# BATTERY_BOARD.net
KiCad netlist of a schematic drawn in Altium Designer
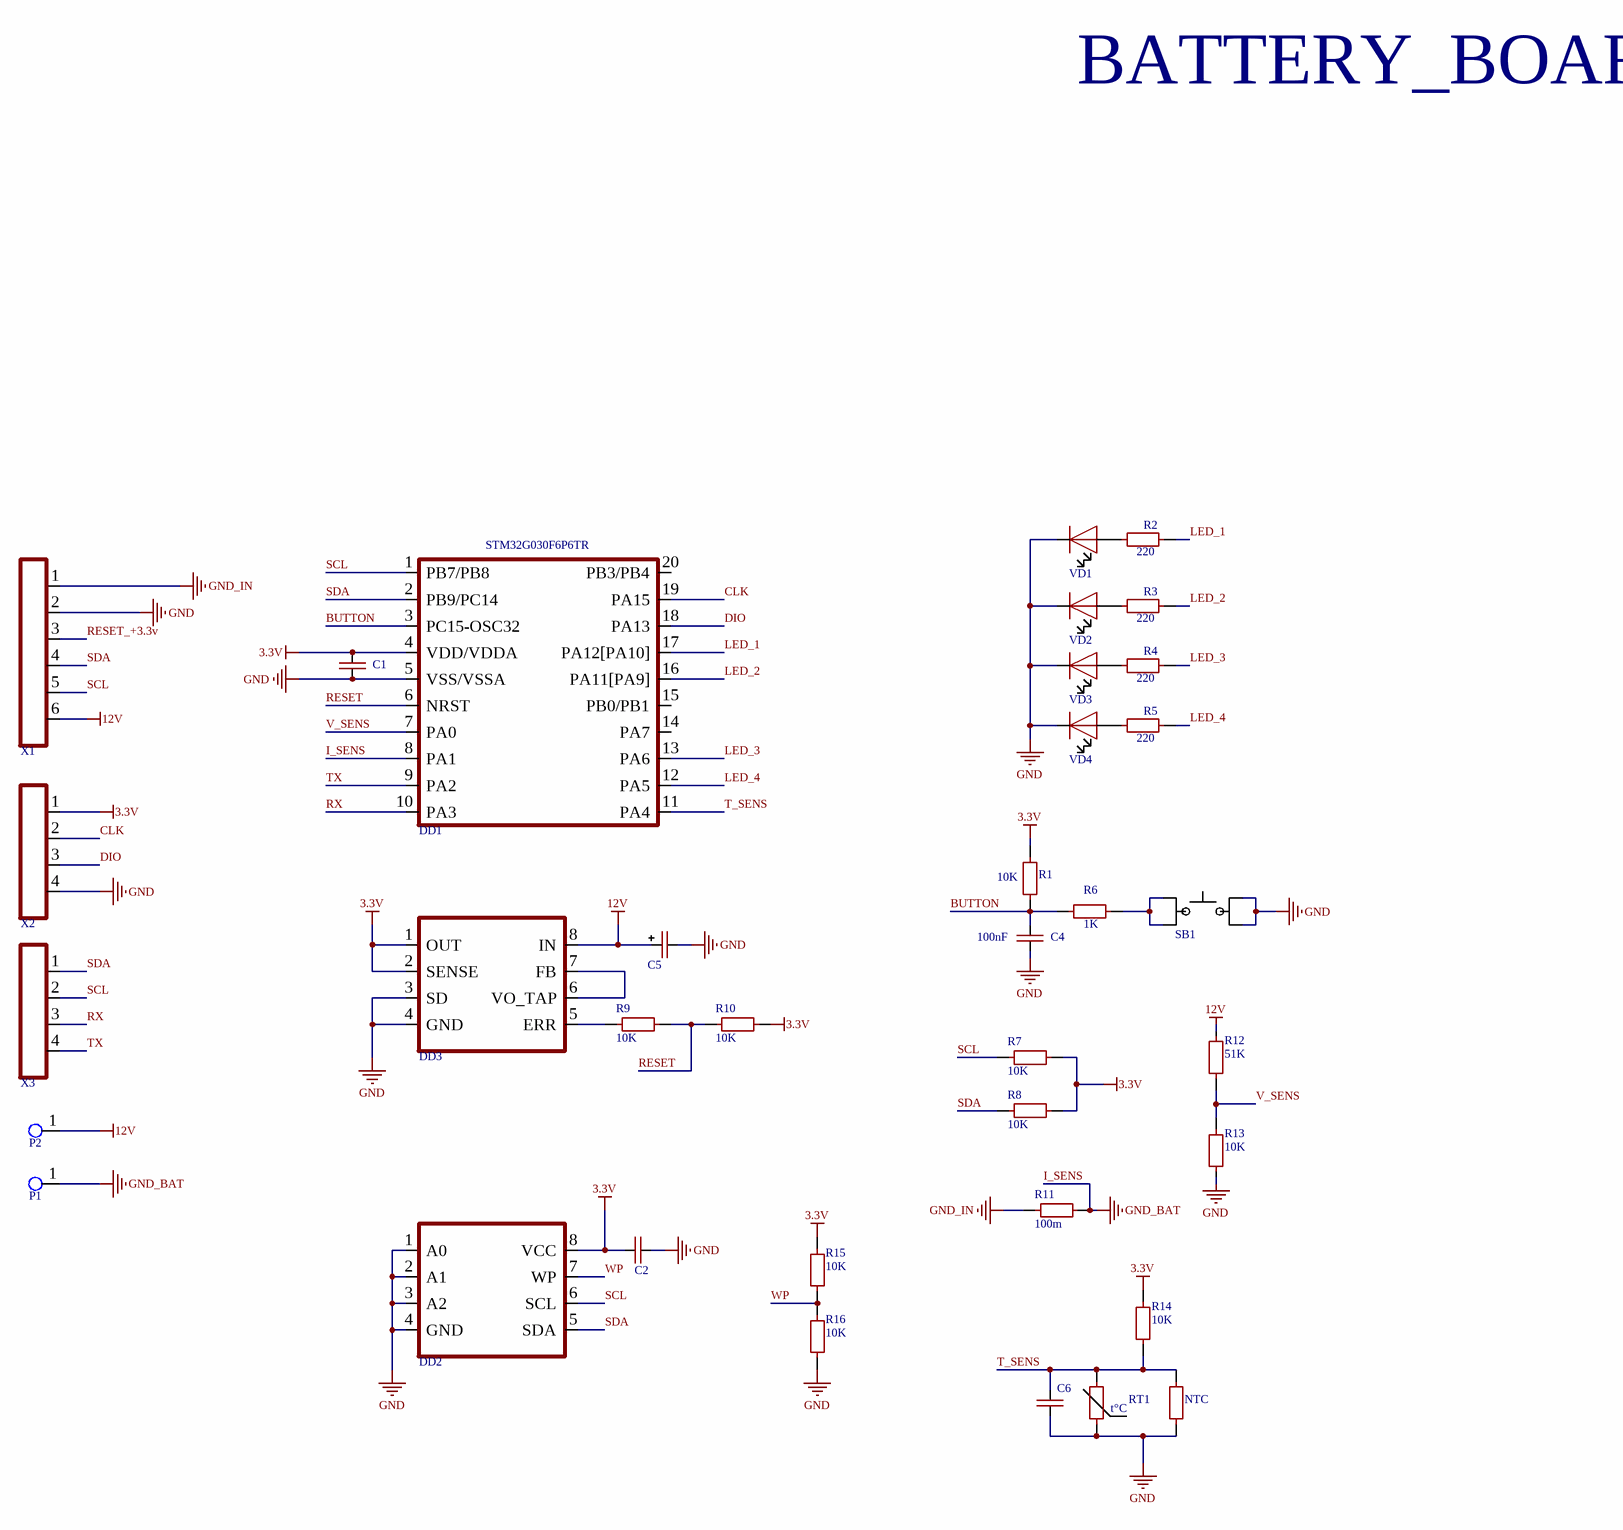
[diagram p0: BATTERY_BOARD.SchDoc]

(export (version "E")
  (design (tool "Eeschema 10.0.6"))
  (components
    (comp (ref "C1")
      (value "CAP-NON-POLAR")
      (footprint "CAP-0603")
      (libsource (lib "PASSIVE_COMPONENTS") (part "CAP-NON-POLAR"))
    )
    (comp (ref "C2")
      (value "CAP-NON-POLAR")
      (footprint "CAP-0603")
      (libsource (lib "PASSIVE_COMPONENTS") (part "CAP-NON-POLAR"))
    )
    (comp (ref "C4")
      (value "100nF")
      (footprint "CAP-0603")
      (libsource (lib "PASSIVE_COMPONENTS") (part "CAP-NON-POLAR"))
    )
    (comp (ref "C5")
      (value "CAP-POLAR")
      (footprint "CAP-TAN-C")
      (libsource (lib "PASSIVE_COMPONENTS") (part "CAP-POLAR"))
    )
    (comp (ref "C6")
      (value "CAP-NON-POLAR")
      (footprint "CAP-0805")
      (libsource (lib "PASSIVE_COMPONENTS") (part "CAP-NON-POLAR"))
    )
    (comp (ref "DD1")
      (value "STM32G030F6P6TR")
      (footprint "TSSOP-20")
      (libsource (lib "STM32G030F6P6TR") (part "STM32G030F6P6TR"))
    )
    (comp (ref "DD2") (value "24C256") (footprint "SO8-150") (libsource (lib "24C256") (part "24C256")))
    (comp (ref "DD3") (value "LP2951") (footprint "SO8-150") (libsource (lib "LP2951") (part "LP2951")))
    (comp (ref "NTC")
      (value "RES-CONST")
      (footprint "RES-0805")
      (libsource (lib "PASSIVE_COMPONENTS") (part "RES-CONST"))
    )
    (comp (ref "P1") (value "Test_Point_PCB") (footprint "Point") (libsource (lib "POINT") (part "POINT")))
    (comp (ref "P2") (value "Test_Point_PCB") (footprint "Point") (libsource (lib "POINT") (part "POINT")))
    (comp (ref "R1")
      (value "10K")
      (footprint "RES-0603")
      (libsource (lib "PASSIVE_COMPONENTS") (part "RES-CONST"))
    )
    (comp (ref "R2")
      (value "220")
      (footprint "RES-0603")
      (libsource (lib "PASSIVE_COMPONENTS") (part "RES-CONST"))
    )
    (comp (ref "R3")
      (value "220")
      (footprint "RES-0603")
      (libsource (lib "PASSIVE_COMPONENTS") (part "RES-CONST"))
    )
    (comp (ref "R4")
      (value "220")
      (footprint "RES-0603")
      (libsource (lib "PASSIVE_COMPONENTS") (part "RES-CONST"))
    )
    (comp (ref "R5")
      (value "220")
      (footprint "RES-0603")
      (libsource (lib "PASSIVE_COMPONENTS") (part "RES-CONST"))
    )
    (comp (ref "R6")
      (value "1K")
      (footprint "RES-0603")
      (libsource (lib "PASSIVE_COMPONENTS") (part "RES-CONST"))
    )
    (comp (ref "R7")
      (value "10K")
      (footprint "RES-0603")
      (libsource (lib "PASSIVE_COMPONENTS") (part "RES-CONST"))
    )
    (comp (ref "R8")
      (value "10K")
      (footprint "RES-0603")
      (libsource (lib "PASSIVE_COMPONENTS") (part "RES-CONST"))
    )
    (comp (ref "R9")
      (value "10K")
      (footprint "RES-0603")
      (libsource (lib "PASSIVE_COMPONENTS") (part "RES-CONST"))
    )
    (comp (ref "R10")
      (value "10K")
      (footprint "RES-0603")
      (libsource (lib "PASSIVE_COMPONENTS") (part "RES-CONST"))
    )
    (comp (ref "R11")
      (value "100m")
      (footprint "RES-2512")
      (libsource (lib "PASSIVE_COMPONENTS") (part "RES-CONST"))
    )
    (comp (ref "R12")
      (value "51K")
      (footprint "RES-0603")
      (libsource (lib "PASSIVE_COMPONENTS") (part "RES-CONST"))
    )
    (comp (ref "R13")
      (value "10K")
      (footprint "RES-0603")
      (libsource (lib "PASSIVE_COMPONENTS") (part "RES-CONST"))
    )
    (comp (ref "R14")
      (value "10K")
      (footprint "RES-0603")
      (libsource (lib "PASSIVE_COMPONENTS") (part "RES-CONST"))
    )
    (comp (ref "R15")
      (value "10K")
      (footprint "RES-0603")
      (libsource (lib "PASSIVE_COMPONENTS") (part "RES-CONST"))
    )
    (comp (ref "R16")
      (value "10K")
      (footprint "RES-0603")
      (libsource (lib "PASSIVE_COMPONENTS") (part "RES-CONST"))
    )
    (comp (ref "RT1") (value "RES-TEMP") (footprint "NTC_MF52") (libsource (lib "NTC") (part "RES-TEMP")))
    (comp (ref "SB1")
      (value "BUTTON-TACT-4PIN")
      (footprint "TACTB-6x6 SMD")
      (libsource (lib "TACTB-6x6 SMD") (part "BUTTON-TACT-4PIN"))
    )
    (comp (ref "VD1") (value "LED") (footprint "LED-0603") (libsource (lib "LED") (part "LED")))
    (comp (ref "VD2") (value "LED") (footprint "LED-0603") (libsource (lib "LED") (part "LED")))
    (comp (ref "VD3") (value "LED") (footprint "LED-0603") (libsource (lib "LED") (part "LED")))
    (comp (ref "VD4") (value "LED") (footprint "LED-0603") (libsource (lib "LED") (part "LED")))
    (comp (ref "X1")
      (value "CONN-6-PIN")
      (footprint "CON_6PIN_BATT_DEFIBRILLATOR")
      (libsource (lib "CON_6PIN_BATT_DEFIBRILLATOR") (part "CONN-6-PIN"))
    )
    (comp (ref "X2")
      (value "CONN-4-PIN")
      (footprint "CONN-PLS-4-2.54mm")
      (libsource (lib "CONNECTORS") (part "CONN-4-PIN"))
    )
    (comp (ref "X3")
      (value "CONN-4-PIN")
      (footprint "CONN-PLS-4-2.54mm")
      (libsource (lib "CONNECTORS") (part "CONN-4-PIN"))
    )
  )
  (nets
    (net (code "1") (name "/BUTTON") (class "Default")
      (node (ref "C4") (pin "2") (pinfunction "2_2") (pintype "passive"))
      (node (ref "DD1") (pin "3") (pinfunction "PC15-OSC32_3") (pintype "passive"))
      (node (ref "R1") (pin "1") (pinfunction "1_1") (pintype "passive"))
      (node (ref "R6") (pin "1") (pinfunction "1_1") (pintype "passive"))
    )
    (net (code "2") (name "/CLK") (class "Default")
      (node (ref "DD1") (pin "19") (pinfunction "PA15_19") (pintype "passive"))
      (node (ref "X2") (pin "2") (pinfunction "2_2") (pintype "passive"))
    )
    (net (code "3") (name "/DIO") (class "Default")
      (node (ref "DD1") (pin "18") (pinfunction "PA13_18") (pintype "passive"))
      (node (ref "X2") (pin "3") (pinfunction "3_3") (pintype "passive"))
    )
    (net (code "4") (name "/LED_1") (class "Default")
      (node (ref "DD1") (pin "17") (pinfunction "PA12[PA10]_17") (pintype "passive"))
      (node (ref "R2") (pin "2") (pinfunction "2_2") (pintype "passive"))
    )
    (net (code "5") (name "/LED_2") (class "Default")
      (node (ref "DD1") (pin "16") (pinfunction "PA11[PA9]_16") (pintype "passive"))
      (node (ref "R3") (pin "2") (pinfunction "2_2") (pintype "passive"))
    )
    (net (code "6") (name "/LED_3") (class "Default")
      (node (ref "DD1") (pin "13") (pinfunction "PA6_13") (pintype "passive"))
      (node (ref "R4") (pin "2") (pinfunction "2_2") (pintype "passive"))
    )
    (net (code "7") (name "/LED_4") (class "Default")
      (node (ref "DD1") (pin "12") (pinfunction "PA5_12") (pintype "passive"))
      (node (ref "R5") (pin "2") (pinfunction "2_2") (pintype "passive"))
    )
    (net (code "8") (name "/RESET") (class "Default")
      (node (ref "DD1") (pin "6") (pinfunction "NRST_6") (pintype "passive"))
      (node (ref "R10") (pin "2") (pinfunction "2_2") (pintype "passive"))
      (node (ref "R9") (pin "1") (pinfunction "1_1") (pintype "passive"))
    )
    (net (code "9") (name "/RESET_+3.3v") (class "Default")
      (node (ref "X1") (pin "3") (pinfunction "3_3") (pintype "passive"))
    )
    (net (code "10") (name "/RX") (class "Default")
      (node (ref "DD1") (pin "10") (pinfunction "PA3_10") (pintype "passive"))
      (node (ref "X3") (pin "3") (pinfunction "3_3") (pintype "passive"))
    )
    (net (code "11") (name "/SCL") (class "Default")
      (node (ref "DD1") (pin "1") (pinfunction "PB7/PB8_1") (pintype "passive"))
      (node (ref "DD2") (pin "6") (pinfunction "SCL_6") (pintype "passive"))
      (node (ref "R7") (pin "2") (pinfunction "2_2") (pintype "passive"))
      (node (ref "X1") (pin "5") (pinfunction "5_5") (pintype "passive"))
      (node (ref "X3") (pin "2") (pinfunction "2_2") (pintype "passive"))
    )
    (net (code "12") (name "/SDA") (class "Default")
      (node (ref "DD1") (pin "2") (pinfunction "PB9/PC14_2") (pintype "passive"))
      (node (ref "DD2") (pin "5") (pinfunction "SDA_5") (pintype "passive"))
      (node (ref "R8") (pin "2") (pinfunction "2_2") (pintype "passive"))
      (node (ref "X1") (pin "4") (pinfunction "4_4") (pintype "passive"))
      (node (ref "X3") (pin "1") (pinfunction "1_1") (pintype "passive"))
    )
    (net (code "13") (name "/TX") (class "Default")
      (node (ref "DD1") (pin "9") (pinfunction "PA2_9") (pintype "passive"))
      (node (ref "X3") (pin "4") (pinfunction "4_4") (pintype "passive"))
    )
    (net (code "14") (name "/T_SENS") (class "Default")
      (node (ref "C6") (pin "2") (pinfunction "2_2") (pintype "passive"))
      (node (ref "DD1") (pin "11") (pinfunction "PA4_11") (pintype "passive"))
      (node (ref "NTC") (pin "2") (pinfunction "2_2") (pintype "passive"))
      (node (ref "R14") (pin "2") (pinfunction "2_2") (pintype "passive"))
      (node (ref "RT1") (pin "2") (pinfunction "2_2") (pintype "passive"))
    )
    (net (code "15") (name "/V_SENS") (class "Default")
      (node (ref "DD1") (pin "7") (pinfunction "PA0_7") (pintype "passive"))
      (node (ref "R12") (pin "2") (pinfunction "2_2") (pintype "passive"))
      (node (ref "R13") (pin "1") (pinfunction "1_1") (pintype "passive"))
    )
    (net (code "16") (name "/WP") (class "Default")
      (node (ref "DD2") (pin "7") (pinfunction "WP_7") (pintype "passive"))
      (node (ref "R15") (pin "2") (pinfunction "2_2") (pintype "passive"))
      (node (ref "R16") (pin "1") (pinfunction "1_1") (pintype "passive"))
    )
    (net (code "17") (name "3.3V") (class "Default")
      (node (ref "C1") (pin "2") (pinfunction "2_2") (pintype "passive"))
      (node (ref "C2") (pin "2") (pinfunction "2_2") (pintype "passive"))
      (node (ref "DD1") (pin "4") (pinfunction "VDD/VDDA_4") (pintype "passive"))
      (node (ref "DD2") (pin "8") (pinfunction "VCC_8") (pintype "passive"))
      (node (ref "DD3") (pin "1") (pinfunction "OUT_1") (pintype "passive"))
      (node (ref "DD3") (pin "2") (pinfunction "SENSE_2") (pintype "passive"))
      (node (ref "R1") (pin "2") (pinfunction "2_2") (pintype "passive"))
      (node (ref "R10") (pin "1") (pinfunction "1_1") (pintype "passive"))
      (node (ref "R14") (pin "1") (pinfunction "1_1") (pintype "passive"))
      (node (ref "R15") (pin "1") (pinfunction "1_1") (pintype "passive"))
      (node (ref "R7") (pin "1") (pinfunction "1_1") (pintype "passive"))
      (node (ref "R8") (pin "1") (pinfunction "1_1") (pintype "passive"))
      (node (ref "X2") (pin "1") (pinfunction "1_1") (pintype "passive"))
    )
    (net (code "18") (name "12V") (class "Default")
      (node (ref "C5") (pin "1") (pinfunction "+_1") (pintype "passive"))
      (node (ref "DD3") (pin "8") (pinfunction "IN_8") (pintype "passive"))
      (node (ref "P2") (pin "1") (pinfunction "G9_1") (pintype "passive"))
      (node (ref "R12") (pin "1") (pinfunction "1_1") (pintype "passive"))
      (node (ref "X1") (pin "6") (pinfunction "6_6") (pintype "passive"))
    )
    (net (code "19") (name "GND") (class "Default")
      (node (ref "C1") (pin "1") (pinfunction "1_1") (pintype "passive"))
      (node (ref "C2") (pin "1") (pinfunction "1_1") (pintype "passive"))
      (node (ref "C4") (pin "1") (pinfunction "1_1") (pintype "passive"))
      (node (ref "C5") (pin "2") (pinfunction "-_2") (pintype "passive"))
      (node (ref "C6") (pin "1") (pinfunction "1_1") (pintype "passive"))
      (node (ref "DD1") (pin "5") (pinfunction "VSS/VSSA_5") (pintype "passive"))
      (node (ref "DD2") (pin "1") (pinfunction "A0_1") (pintype "passive"))
      (node (ref "DD2") (pin "2") (pinfunction "A1_2") (pintype "passive"))
      (node (ref "DD2") (pin "3") (pinfunction "A2_3") (pintype "passive"))
      (node (ref "DD2") (pin "4") (pinfunction "GND_4") (pintype "passive"))
      (node (ref "DD3") (pin "3") (pinfunction "SD_3") (pintype "passive"))
      (node (ref "DD3") (pin "4") (pinfunction "GND_4") (pintype "passive"))
      (node (ref "NTC") (pin "1") (pinfunction "1_1") (pintype "passive"))
      (node (ref "R13") (pin "2") (pinfunction "2_2") (pintype "passive"))
      (node (ref "R16") (pin "2") (pinfunction "2_2") (pintype "passive"))
      (node (ref "RT1") (pin "1") (pinfunction "1_1") (pintype "passive"))
      (node (ref "SB1") (pin "3") (pintype "passive"))
      (node (ref "SB1") (pin "4") (pintype "passive"))
      (node (ref "VD1") (pin "1") (pinfunction "C_1") (pintype "passive"))
      (node (ref "VD2") (pin "1") (pinfunction "C_1") (pintype "passive"))
      (node (ref "VD3") (pin "1") (pinfunction "C_1") (pintype "passive"))
      (node (ref "VD4") (pin "1") (pinfunction "C_1") (pintype "passive"))
      (node (ref "X1") (pin "2") (pinfunction "2_2") (pintype "passive"))
      (node (ref "X2") (pin "4") (pinfunction "4_4") (pintype "passive"))
    )
    (net (code "20") (name "GND_BAT") (class "Default")
      (node (ref "DD1") (pin "8") (pinfunction "PA1_8") (pintype "passive"))
      (node (ref "P1") (pin "1") (pinfunction "G9_1") (pintype "passive"))
      (node (ref "R11") (pin "2") (pinfunction "2_2") (pintype "passive"))
    )
    (net (code "21") (name "GND_IN") (class "Default")
      (node (ref "R11") (pin "1") (pinfunction "1_1") (pintype "passive"))
      (node (ref "X1") (pin "1") (pinfunction "1_1") (pintype "passive"))
    )
    (net (code "22") (name "Net-(DD3-ERR)") (class "Default")
      (node (ref "DD3") (pin "5") (pinfunction "ERR_5") (pintype "passive"))
      (node (ref "R9") (pin "2") (pinfunction "2_2") (pintype "passive"))
    )
    (net (code "23") (name "Net-(DD3-FB)") (class "Default")
      (node (ref "DD3") (pin "6") (pinfunction "VO_TAP_6") (pintype "passive"))
      (node (ref "DD3") (pin "7") (pinfunction "FB_7") (pintype "passive"))
    )
    (net (code "24") (name "Net-(R6-Pad2)") (class "Default")
      (node (ref "R6") (pin "2") (pinfunction "2_2") (pintype "passive"))
      (node (ref "SB1") (pin "1") (pintype "passive"))
      (node (ref "SB1") (pin "2") (pintype "passive"))
    )
    (net (code "25") (name "Net-(VD1-A)") (class "Default")
      (node (ref "R2") (pin "1") (pinfunction "1_1") (pintype "passive"))
      (node (ref "VD1") (pin "2") (pinfunction "A_2") (pintype "passive"))
    )
    (net (code "26") (name "Net-(VD2-A)") (class "Default")
      (node (ref "R3") (pin "1") (pinfunction "1_1") (pintype "passive"))
      (node (ref "VD2") (pin "2") (pinfunction "A_2") (pintype "passive"))
    )
    (net (code "27") (name "Net-(VD3-A)") (class "Default")
      (node (ref "R4") (pin "1") (pinfunction "1_1") (pintype "passive"))
      (node (ref "VD3") (pin "2") (pinfunction "A_2") (pintype "passive"))
    )
    (net (code "28") (name "Net-(VD4-A)") (class "Default")
      (node (ref "R5") (pin "1") (pinfunction "1_1") (pintype "passive"))
      (node (ref "VD4") (pin "2") (pinfunction "A_2") (pintype "passive"))
    )
    (net (code "29") (name "unconnected-(DD1-PA7-Pad14)") (class "Default")
      (node (ref "DD1") (pin "14") (pinfunction "PA7_14") (pintype "passive"))
    )
    (net (code "30") (name "unconnected-(DD1-PB0{slash}PB1-Pad15)") (class "Default")
      (node (ref "DD1") (pin "15") (pinfunction "PB0/PB1_15") (pintype "passive"))
    )
    (net (code "31") (name "unconnected-(DD1-PB3{slash}PB4-Pad20)") (class "Default")
      (node (ref "DD1") (pin "20") (pinfunction "PB3/PB4_20") (pintype "passive"))
    )
  )
)
